# MCU1.net
KiCad netlist of a schematic drawn in Altium Designer
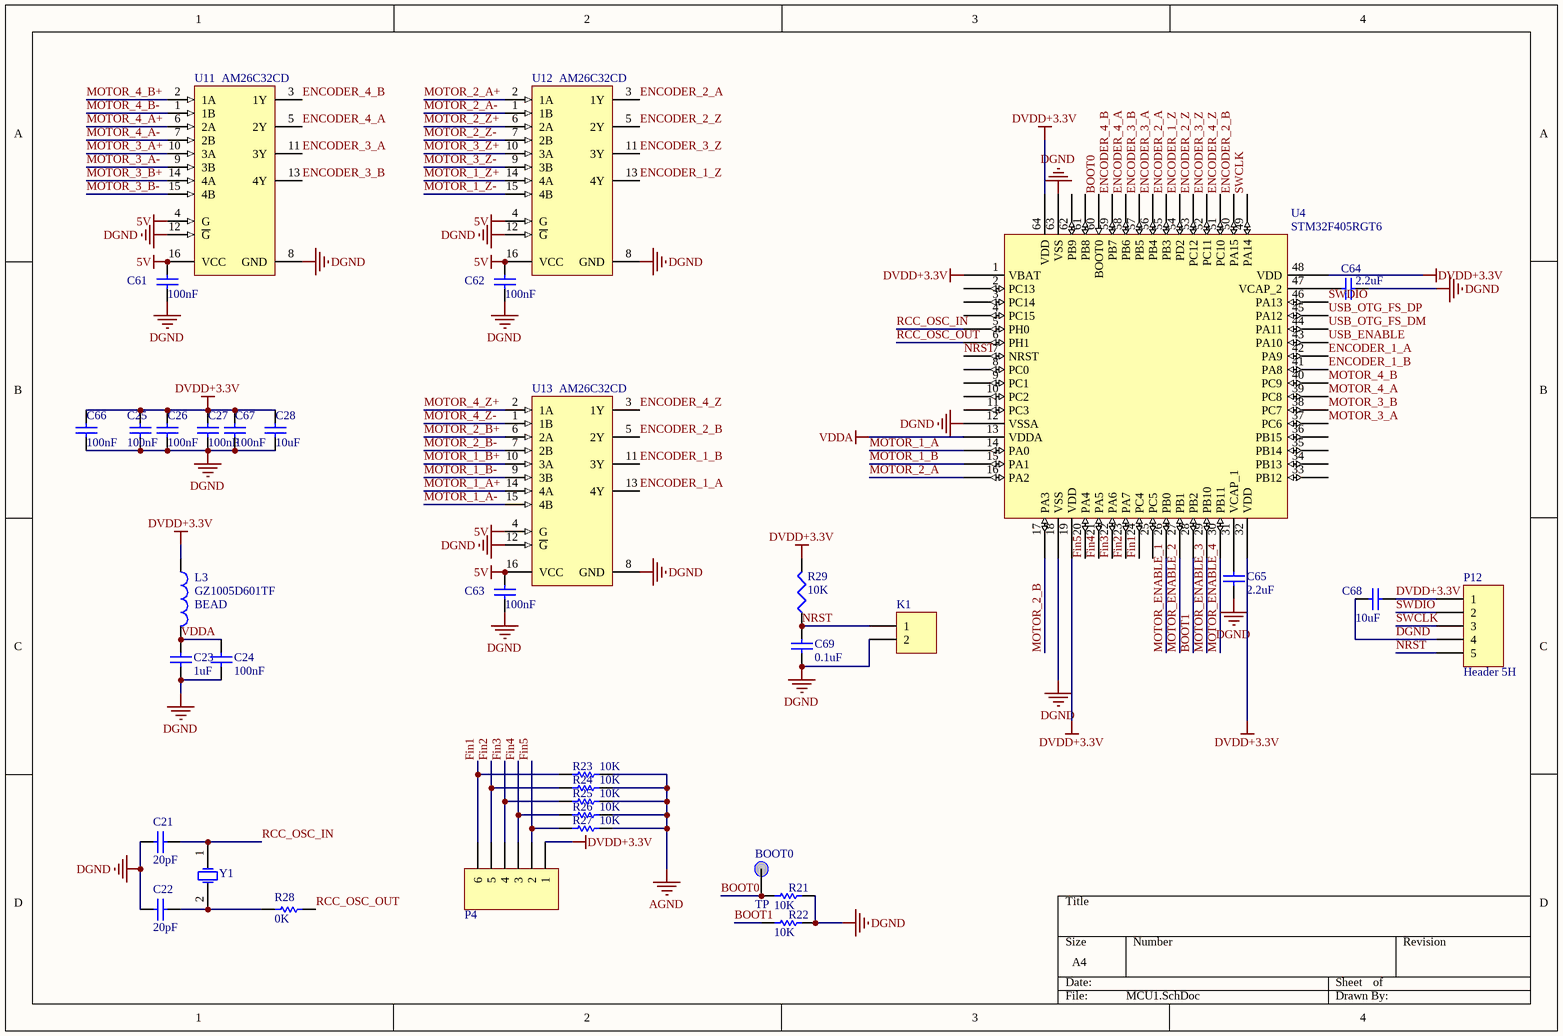
[diagram p0: MCU1.SchDoc]

(export (version "E")
  (design (tool "Eeschema 10.0.6"))
  (components
    (comp (ref "BOOT0") (value "TP") (footprint "TestPort") (libsource (lib "CTs_FYF") (part "TestPoint")))
    (comp (ref "C21")
      (value "20pF")
      (footprint "0402")
      (description "Capacitor")
      (fields (field (name "PUBLISHER") "Altium Limited"))
      (libsource (lib "Miscellaneous Devices") (part "Cap"))
    )
    (comp (ref "C22")
      (value "20pF")
      (footprint "0402")
      (description "Capacitor")
      (fields (field (name "PUBLISHER") "Altium Limited"))
      (libsource (lib "Miscellaneous Devices") (part "Cap"))
    )
    (comp (ref "C23")
      (value "1uF")
      (footprint "1608[0603]")
      (description "Capacitor")
      (fields (field (name "PUBLISHER") "Altium Limited"))
      (libsource (lib "Miscellaneous Devices") (part "Cap"))
    )
    (comp (ref "C24")
      (value "100nF")
      (footprint "1608[0603]")
      (description "Capacitor")
      (fields (field (name "PUBLISHER") "Altium Limited"))
      (libsource (lib "Miscellaneous Devices") (part "Cap"))
    )
    (comp (ref "C25")
      (value "100nF")
      (footprint "1608[0603]")
      (description "Capacitor")
      (fields (field (name "PUBLISHER") "Altium Limited"))
      (libsource (lib "Miscellaneous Devices") (part "Cap"))
    )
    (comp (ref "C26")
      (value "100nF")
      (footprint "1608[0603]")
      (description "Capacitor")
      (fields (field (name "PUBLISHER") "Altium Limited"))
      (libsource (lib "Miscellaneous Devices") (part "Cap"))
    )
    (comp (ref "C27")
      (value "100nF")
      (footprint "1608[0603]")
      (description "Capacitor")
      (fields (field (name "PUBLISHER") "Altium Limited"))
      (libsource (lib "Miscellaneous Devices") (part "Cap"))
    )
    (comp (ref "C28")
      (value "10uF")
      (footprint "1608[0603]")
      (description "Capacitor")
      (fields (field (name "PUBLISHER") "Altium Limited"))
      (libsource (lib "Miscellaneous Devices") (part "Cap"))
    )
    (comp (ref "C61")
      (value "100nF")
      (footprint "1608[0603]")
      (description "Capacitor")
      (fields (field (name "PUBLISHER") "Altium Limited"))
      (libsource (lib "Miscellaneous Devices") (part "Cap"))
    )
    (comp (ref "C62")
      (value "100nF")
      (footprint "1608[0603]")
      (description "Capacitor")
      (fields (field (name "PUBLISHER") "Altium Limited"))
      (libsource (lib "Miscellaneous Devices") (part "Cap"))
    )
    (comp (ref "C63")
      (value "100nF")
      (footprint "1608[0603]")
      (description "Capacitor")
      (fields (field (name "PUBLISHER") "Altium Limited"))
      (libsource (lib "Miscellaneous Devices") (part "Cap"))
    )
    (comp (ref "C64")
      (value "2.2uF")
      (footprint "1608[0603]")
      (description "Capacitor")
      (fields (field (name "PUBLISHER") "Altium Limited"))
      (libsource (lib "Miscellaneous Devices") (part "Cap"))
    )
    (comp (ref "C65")
      (value "2.2uF")
      (footprint "1608[0603]")
      (description "Capacitor")
      (fields (field (name "PUBLISHER") "Altium Limited"))
      (libsource (lib "Miscellaneous Devices") (part "Cap"))
    )
    (comp (ref "C66")
      (value "100nF")
      (footprint "1608[0603]")
      (description "Capacitor")
      (fields (field (name "PUBLISHER") "Altium Limited"))
      (libsource (lib "Miscellaneous Devices") (part "Cap"))
    )
    (comp (ref "C67")
      (value "100nF")
      (footprint "1608[0603]")
      (description "Capacitor")
      (fields (field (name "PUBLISHER") "Altium Limited"))
      (libsource (lib "Miscellaneous Devices") (part "Cap"))
    )
    (comp (ref "C68")
      (value "10uF")
      (footprint "1608[0603]")
      (description "Capacitor")
      (fields (field (name "PUBLISHER") "Altium Limited"))
      (libsource (lib "Miscellaneous Devices") (part "Cap"))
    )
    (comp (ref "C69")
      (value "0.1uF")
      (footprint "1608[0603]")
      (description "Capacitor")
      (fields (field (name "PUBLISHER") "Altium Limited"))
      (libsource (lib "Miscellaneous Devices") (part "Cap"))
    )
    (comp (ref "K1")
      (value "Header 2")
      (footprint "Button")
      (description "Header, 2-Pin")
      (fields (field (name "PUBLISHER") "Altium Limited"))
      (libsource (lib "Miscellaneous Connectors") (part "Header 2"))
    )
    (comp (ref "L3")
      (value "GZ1005D601TF")
      (footprint "0402-A")
      (description "Inductor")
      (fields (field (name "PUBLISHER") "Altium Limited"))
      (libsource (lib "Miscellaneous Devices") (part "Inductor"))
    )
    (comp (ref "P4")
      (value "Header 6")
      (footprint "HDR1X6")
      (description "Header, 6-Pin")
      (fields (field (name "PUBLISHER") "Altium Limited"))
      (libsource (lib "Miscellaneous Connectors") (part "Header 6"))
    )
    (comp (ref "P12")
      (value "Header 5H")
      (footprint "HDR1X5H")
      (description "Header, 5-Pin, Right Angle")
      (fields (field (name "PUBLISHER") "Altium Limited"))
      (libsource (lib "Miscellaneous Connectors") (part "Header 5H"))
    )
    (comp (ref "R21")
      (value "10K")
      (footprint "J1-0603")
      (description "Resistor")
      (fields (field (name "PUBLISHER") "Altium Limited"))
      (libsource (lib "Miscellaneous Devices") (part "Res1"))
    )
    (comp (ref "R22")
      (value "10K")
      (footprint "J1-0603")
      (description "Resistor")
      (fields (field (name "PUBLISHER") "Altium Limited"))
      (libsource (lib "Miscellaneous Devices") (part "Res1"))
    )
    (comp (ref "R23")
      (value "10K")
      (footprint "RES[0402]")
      (description "Resistor")
      (fields (field (name "PUBLISHER") "Altium Limited"))
      (libsource (lib "Miscellaneous Devices") (part "Res1"))
    )
    (comp (ref "R24")
      (value "10K")
      (footprint "RES[0402]")
      (description "Resistor")
      (fields (field (name "PUBLISHER") "Altium Limited"))
      (libsource (lib "Miscellaneous Devices") (part "Res1"))
    )
    (comp (ref "R25")
      (value "10K")
      (footprint "RES[0402]")
      (description "Resistor")
      (fields (field (name "PUBLISHER") "Altium Limited"))
      (libsource (lib "Miscellaneous Devices") (part "Res1"))
    )
    (comp (ref "R26")
      (value "10K")
      (footprint "RES[0402]")
      (description "Resistor")
      (fields (field (name "PUBLISHER") "Altium Limited"))
      (libsource (lib "Miscellaneous Devices") (part "Res1"))
    )
    (comp (ref "R27")
      (value "10K")
      (footprint "RES[0402]")
      (description "Resistor")
      (fields (field (name "PUBLISHER") "Altium Limited"))
      (libsource (lib "Miscellaneous Devices") (part "Res1"))
    )
    (comp (ref "R28")
      (value "0K")
      (footprint "J1-0603")
      (description "Resistor")
      (fields (field (name "PUBLISHER") "Altium Limited"))
      (libsource (lib "Miscellaneous Devices") (part "Res1"))
    )
    (comp (ref "R29")
      (value "10K")
      (footprint "J1-0603")
      (description "Resistor")
      (fields (field (name "PUBLISHER") "Altium Limited"))
      (libsource (lib "Miscellaneous Devices") (part "Res3"))
    )
    (comp (ref "U4")
      (value "STM32F405RGT6")
      (footprint "STM32F405RGT6")
      (description "IC MCU 32BIT 1MB FLASH 64LQFP")
      (libsource (lib "STM32F405RGT6") (part "STM32F405RGT6"))
    )
    (comp (ref "U11")
      (value "AM26C32CD")
      (footprint "D16_L")
      (fields (field (name "MANUFACTURER") "Texas Instruments"))
      (libsource (lib "Texas Instruments Interface RS-422") (part "AM26C32CD"))
    )
    (comp (ref "U12")
      (value "AM26C32CD")
      (footprint "D16_L")
      (fields (field (name "MANUFACTURER") "Texas Instruments"))
      (libsource (lib "Texas Instruments Interface RS-422") (part "AM26C32CD"))
    )
    (comp (ref "U13")
      (value "AM26C32CD")
      (footprint "D16_L")
      (fields (field (name "MANUFACTURER") "Texas Instruments"))
      (libsource (lib "Texas Instruments Interface RS-422") (part "AM26C32CD"))
    )
    (comp (ref "Y1")
      (value "XTAL")
      (footprint "Crystal_HCM49")
      (description "Crystal Oscillator")
      (fields (field (name "PUBLISHER") "Altium Limited"))
      (libsource (lib "Miscellaneous Devices") (part "XTAL"))
    )
  )
  (nets
    (net (code "1") (name "/BOOT0") (class "Default")
      (node (ref "BOOT0") (pin "0") (pinfunction "0_0") (pintype "passive"))
      (node (ref "R21") (pin "1") (pinfunction "1_1") (pintype "passive"))
      (node (ref "U4") (pin "60") (pinfunction "BOOT0_60") (pintype "input"))
    )
    (net (code "2") (name "/BOOT1") (class "Default")
      (node (ref "R22") (pin "1") (pinfunction "1_1") (pintype "passive"))
      (node (ref "U4") (pin "28") (pinfunction "PB2_28") (pintype "bidirectional"))
    )
    (net (code "3") (name "/ENCODER_1_A") (class "Default")
      (node (ref "U13") (pin "13") (pinfunction "4Y_13") (pintype "tri_state"))
      (node (ref "U4") (pin "42") (pinfunction "PA9_42") (pintype "bidirectional"))
    )
    (net (code "4") (name "/ENCODER_1_B") (class "Default")
      (node (ref "U13") (pin "11") (pinfunction "3Y_11") (pintype "tri_state"))
      (node (ref "U4") (pin "41") (pinfunction "PA8_41") (pintype "bidirectional"))
    )
    (net (code "5") (name "/ENCODER_1_Z") (class "Default")
      (node (ref "U12") (pin "13") (pinfunction "4Y_13") (pintype "tri_state"))
      (node (ref "U4") (pin "54") (pinfunction "PD2_54") (pintype "bidirectional"))
    )
    (net (code "6") (name "/ENCODER_2_A") (class "Default")
      (node (ref "U12") (pin "3") (pinfunction "1Y_3") (pintype "tri_state"))
      (node (ref "U4") (pin "55") (pinfunction "PB3_55") (pintype "bidirectional"))
    )
    (net (code "7") (name "/ENCODER_2_B") (class "Default")
      (node (ref "U13") (pin "5") (pinfunction "2Y_5") (pintype "tri_state"))
      (node (ref "U4") (pin "50") (pinfunction "PA15_50") (pintype "bidirectional"))
    )
    (net (code "8") (name "/ENCODER_2_Z") (class "Default")
      (node (ref "U12") (pin "5") (pinfunction "2Y_5") (pintype "tri_state"))
      (node (ref "U4") (pin "53") (pinfunction "PC12_53") (pintype "bidirectional"))
    )
    (net (code "9") (name "/ENCODER_3_A") (class "Default")
      (node (ref "U11") (pin "11") (pinfunction "3Y_11") (pintype "tri_state"))
      (node (ref "U4") (pin "56") (pinfunction "PB4_56") (pintype "bidirectional"))
    )
    (net (code "10") (name "/ENCODER_3_B") (class "Default")
      (node (ref "U11") (pin "13") (pinfunction "4Y_13") (pintype "tri_state"))
      (node (ref "U4") (pin "57") (pinfunction "PB5_57") (pintype "bidirectional"))
    )
    (net (code "11") (name "/ENCODER_3_Z") (class "Default")
      (node (ref "U12") (pin "11") (pinfunction "3Y_11") (pintype "tri_state"))
      (node (ref "U4") (pin "52") (pinfunction "PC11_52") (pintype "bidirectional"))
    )
    (net (code "12") (name "/ENCODER_4_A") (class "Default")
      (node (ref "U11") (pin "5") (pinfunction "2Y_5") (pintype "tri_state"))
      (node (ref "U4") (pin "58") (pinfunction "PB6_58") (pintype "bidirectional"))
    )
    (net (code "13") (name "/ENCODER_4_B") (class "Default")
      (node (ref "U11") (pin "3") (pinfunction "1Y_3") (pintype "tri_state"))
      (node (ref "U4") (pin "59") (pinfunction "PB7_59") (pintype "bidirectional"))
    )
    (net (code "14") (name "/ENCODER_4_Z") (class "Default")
      (node (ref "U13") (pin "3") (pinfunction "1Y_3") (pintype "tri_state"))
      (node (ref "U4") (pin "51") (pinfunction "PC10_51") (pintype "bidirectional"))
    )
    (net (code "15") (name "/Fin1") (class "Default")
      (node (ref "P4") (pin "6") (pinfunction "6_6") (pintype "passive"))
      (node (ref "R23") (pin "1") (pinfunction "1_1") (pintype "passive"))
      (node (ref "U4") (pin "24") (pinfunction "PC4_24") (pintype "bidirectional"))
    )
    (net (code "16") (name "/Fin2") (class "Default")
      (node (ref "P4") (pin "5") (pinfunction "5_5") (pintype "passive"))
      (node (ref "R24") (pin "1") (pinfunction "1_1") (pintype "passive"))
      (node (ref "U4") (pin "23") (pinfunction "PA7_23") (pintype "bidirectional"))
    )
    (net (code "17") (name "/Fin3") (class "Default")
      (node (ref "P4") (pin "4") (pinfunction "4_4") (pintype "passive"))
      (node (ref "R25") (pin "1") (pinfunction "1_1") (pintype "passive"))
      (node (ref "U4") (pin "22") (pinfunction "PA6_22") (pintype "bidirectional"))
    )
    (net (code "18") (name "/Fin4") (class "Default")
      (node (ref "P4") (pin "3") (pinfunction "3_3") (pintype "passive"))
      (node (ref "R26") (pin "1") (pinfunction "1_1") (pintype "passive"))
      (node (ref "U4") (pin "21") (pinfunction "PA5_21") (pintype "bidirectional"))
    )
    (net (code "19") (name "/Fin5") (class "Default")
      (node (ref "P4") (pin "2") (pinfunction "2_2") (pintype "passive"))
      (node (ref "R27") (pin "1") (pinfunction "1_1") (pintype "passive"))
      (node (ref "U4") (pin "20") (pinfunction "PA4_20") (pintype "bidirectional"))
    )
    (net (code "20") (name "/MOTOR_1_A") (class "Default")
      (node (ref "U4") (pin "14") (pinfunction "PA0_14") (pintype "bidirectional"))
    )
    (net (code "21") (name "/MOTOR_1_A+") (class "Default")
      (node (ref "U13") (pin "14") (pinfunction "4A_14") (pintype "input"))
    )
    (net (code "22") (name "/MOTOR_1_A-") (class "Default")
      (node (ref "U13") (pin "15") (pinfunction "4B_15") (pintype "input"))
    )
    (net (code "23") (name "/MOTOR_1_B") (class "Default")
      (node (ref "U4") (pin "15") (pinfunction "PA1_15") (pintype "bidirectional"))
    )
    (net (code "24") (name "/MOTOR_1_B+") (class "Default")
      (node (ref "U13") (pin "10") (pinfunction "3A_10") (pintype "input"))
    )
    (net (code "25") (name "/MOTOR_1_B-") (class "Default")
      (node (ref "U13") (pin "9") (pinfunction "3B_9") (pintype "input"))
    )
    (net (code "26") (name "/MOTOR_1_Z+") (class "Default")
      (node (ref "U12") (pin "14") (pinfunction "4A_14") (pintype "input"))
    )
    (net (code "27") (name "/MOTOR_1_Z-") (class "Default")
      (node (ref "U12") (pin "15") (pinfunction "4B_15") (pintype "input"))
    )
    (net (code "28") (name "/MOTOR_2_A") (class "Default")
      (node (ref "U4") (pin "16") (pinfunction "PA2_16") (pintype "bidirectional"))
    )
    (net (code "29") (name "/MOTOR_2_A+") (class "Default")
      (node (ref "U12") (pin "2") (pinfunction "1A_2") (pintype "input"))
    )
    (net (code "30") (name "/MOTOR_2_A-") (class "Default")
      (node (ref "U12") (pin "1") (pinfunction "1B_1") (pintype "input"))
    )
    (net (code "31") (name "/MOTOR_2_B") (class "Default")
      (node (ref "U4") (pin "17") (pinfunction "PA3_17") (pintype "bidirectional"))
    )
    (net (code "32") (name "/MOTOR_2_B+") (class "Default")
      (node (ref "U13") (pin "6") (pinfunction "2A_6") (pintype "input"))
    )
    (net (code "33") (name "/MOTOR_2_B-") (class "Default")
      (node (ref "U13") (pin "7") (pinfunction "2B_7") (pintype "input"))
    )
    (net (code "34") (name "/MOTOR_2_Z+") (class "Default")
      (node (ref "U12") (pin "6") (pinfunction "2A_6") (pintype "input"))
    )
    (net (code "35") (name "/MOTOR_2_Z-") (class "Default")
      (node (ref "U12") (pin "7") (pinfunction "2B_7") (pintype "input"))
    )
    (net (code "36") (name "/MOTOR_3_A") (class "Default")
      (node (ref "U4") (pin "37") (pinfunction "PC6_37") (pintype "bidirectional"))
    )
    (net (code "37") (name "/MOTOR_3_A+") (class "Default")
      (node (ref "U11") (pin "10") (pinfunction "3A_10") (pintype "input"))
    )
    (net (code "38") (name "/MOTOR_3_A-") (class "Default")
      (node (ref "U11") (pin "9") (pinfunction "3B_9") (pintype "input"))
    )
    (net (code "39") (name "/MOTOR_3_B") (class "Default")
      (node (ref "U4") (pin "38") (pinfunction "PC7_38") (pintype "bidirectional"))
    )
    (net (code "40") (name "/MOTOR_3_B+") (class "Default")
      (node (ref "U11") (pin "14") (pinfunction "4A_14") (pintype "input"))
    )
    (net (code "41") (name "/MOTOR_3_B-") (class "Default")
      (node (ref "U11") (pin "15") (pinfunction "4B_15") (pintype "input"))
    )
    (net (code "42") (name "/MOTOR_3_Z+") (class "Default")
      (node (ref "U12") (pin "10") (pinfunction "3A_10") (pintype "input"))
    )
    (net (code "43") (name "/MOTOR_3_Z-") (class "Default")
      (node (ref "U12") (pin "9") (pinfunction "3B_9") (pintype "input"))
    )
    (net (code "44") (name "/MOTOR_4_A") (class "Default")
      (node (ref "U4") (pin "39") (pinfunction "PC8_39") (pintype "bidirectional"))
    )
    (net (code "45") (name "/MOTOR_4_A+") (class "Default")
      (node (ref "U11") (pin "6") (pinfunction "2A_6") (pintype "input"))
    )
    (net (code "46") (name "/MOTOR_4_A-") (class "Default")
      (node (ref "U11") (pin "7") (pinfunction "2B_7") (pintype "input"))
    )
    (net (code "47") (name "/MOTOR_4_B") (class "Default")
      (node (ref "U4") (pin "40") (pinfunction "PC9_40") (pintype "bidirectional"))
    )
    (net (code "48") (name "/MOTOR_4_B+") (class "Default")
      (node (ref "U11") (pin "2") (pinfunction "1A_2") (pintype "input"))
    )
    (net (code "49") (name "/MOTOR_4_B-") (class "Default")
      (node (ref "U11") (pin "1") (pinfunction "1B_1") (pintype "input"))
    )
    (net (code "50") (name "/MOTOR_4_Z+") (class "Default")
      (node (ref "U13") (pin "2") (pinfunction "1A_2") (pintype "input"))
    )
    (net (code "51") (name "/MOTOR_4_Z-") (class "Default")
      (node (ref "U13") (pin "1") (pinfunction "1B_1") (pintype "input"))
    )
    (net (code "52") (name "/MOTOR_ENABLE_1") (class "Default")
      (node (ref "U4") (pin "26") (pinfunction "PB0_26") (pintype "bidirectional"))
    )
    (net (code "53") (name "/MOTOR_ENABLE_2") (class "Default")
      (node (ref "U4") (pin "27") (pinfunction "PB1_27") (pintype "bidirectional"))
    )
    (net (code "54") (name "/MOTOR_ENABLE_3") (class "Default")
      (node (ref "U4") (pin "29") (pinfunction "PB10_29") (pintype "bidirectional"))
    )
    (net (code "55") (name "/MOTOR_ENABLE_4") (class "Default")
      (node (ref "U4") (pin "30") (pinfunction "PB11_30") (pintype "bidirectional"))
    )
    (net (code "56") (name "/NRST") (class "Default")
      (node (ref "C69") (pin "2") (pinfunction "2_2") (pintype "passive"))
      (node (ref "K1") (pin "1") (pinfunction "1_1") (pintype "passive"))
      (node (ref "P12") (pin "5") (pinfunction "5_5") (pintype "passive"))
      (node (ref "R29") (pin "1") (pinfunction "1_1") (pintype "passive"))
      (node (ref "U4") (pin "7") (pinfunction "NRST_7") (pintype "bidirectional"))
    )
    (net (code "57") (name "/RCC_OSC_IN") (class "Default")
      (node (ref "C21") (pin "2") (pinfunction "2_2") (pintype "passive"))
      (node (ref "U4") (pin "5") (pinfunction "PH0_5") (pintype "bidirectional"))
      (node (ref "Y1") (pin "1") (pinfunction "OSC1_1") (pintype "passive"))
    )
    (net (code "58") (name "/RCC_OSC_OUT") (class "Default")
      (node (ref "R28") (pin "2") (pinfunction "2_2") (pintype "passive"))
      (node (ref "U4") (pin "6") (pinfunction "PH1_6") (pintype "bidirectional"))
    )
    (net (code "59") (name "/SWCLK") (class "Default")
      (node (ref "P12") (pin "3") (pinfunction "3_3") (pintype "passive"))
      (node (ref "U4") (pin "49") (pinfunction "PA14_49") (pintype "bidirectional"))
    )
    (net (code "60") (name "/SWDIO") (class "Default")
      (node (ref "P12") (pin "2") (pinfunction "2_2") (pintype "passive"))
      (node (ref "U4") (pin "46") (pinfunction "PA13_46") (pintype "bidirectional"))
    )
    (net (code "61") (name "/USB_ENABLE") (class "Default")
      (node (ref "U4") (pin "43") (pinfunction "PA10_43") (pintype "bidirectional"))
    )
    (net (code "62") (name "/USB_OTG_FS_DM") (class "Default")
      (node (ref "U4") (pin "44") (pinfunction "PA11_44") (pintype "bidirectional"))
    )
    (net (code "63") (name "/USB_OTG_FS_DP") (class "Default")
      (node (ref "U4") (pin "45") (pinfunction "PA12_45") (pintype "bidirectional"))
    )
    (net (code "64") (name "5V") (class "Default")
      (node (ref "C61") (pin "2") (pinfunction "2_2") (pintype "passive"))
      (node (ref "C62") (pin "2") (pinfunction "2_2") (pintype "passive"))
      (node (ref "C63") (pin "2") (pinfunction "2_2") (pintype "passive"))
      (node (ref "U11") (pin "16") (pinfunction "VCC_16") (pintype "power_in"))
      (node (ref "U11") (pin "4") (pinfunction "G_4") (pintype "input"))
      (node (ref "U12") (pin "16") (pinfunction "VCC_16") (pintype "power_in"))
      (node (ref "U12") (pin "4") (pinfunction "G_4") (pintype "input"))
      (node (ref "U13") (pin "16") (pinfunction "VCC_16") (pintype "power_in"))
      (node (ref "U13") (pin "4") (pinfunction "G_4") (pintype "input"))
    )
    (net (code "65") (name "AGND") (class "Default")
      (node (ref "R23") (pin "2") (pinfunction "2_2") (pintype "passive"))
      (node (ref "R24") (pin "2") (pinfunction "2_2") (pintype "passive"))
      (node (ref "R25") (pin "2") (pinfunction "2_2") (pintype "passive"))
      (node (ref "R26") (pin "2") (pinfunction "2_2") (pintype "passive"))
      (node (ref "R27") (pin "2") (pinfunction "2_2") (pintype "passive"))
    )
    (net (code "66") (name "DGND") (class "Default")
      (node (ref "C21") (pin "1") (pinfunction "1_1") (pintype "passive"))
      (node (ref "C22") (pin "1") (pinfunction "1_1") (pintype "passive"))
      (node (ref "C23") (pin "1") (pinfunction "1_1") (pintype "passive"))
      (node (ref "C24") (pin "1") (pinfunction "1_1") (pintype "passive"))
      (node (ref "C25") (pin "1") (pinfunction "1_1") (pintype "passive"))
      (node (ref "C26") (pin "1") (pinfunction "1_1") (pintype "passive"))
      (node (ref "C27") (pin "1") (pinfunction "1_1") (pintype "passive"))
      (node (ref "C28") (pin "1") (pinfunction "1_1") (pintype "passive"))
      (node (ref "C61") (pin "1") (pinfunction "1_1") (pintype "passive"))
      (node (ref "C62") (pin "1") (pinfunction "1_1") (pintype "passive"))
      (node (ref "C63") (pin "1") (pinfunction "1_1") (pintype "passive"))
      (node (ref "C64") (pin "2") (pinfunction "2_2") (pintype "passive"))
      (node (ref "C65") (pin "1") (pinfunction "1_1") (pintype "passive"))
      (node (ref "C66") (pin "1") (pinfunction "1_1") (pintype "passive"))
      (node (ref "C67") (pin "1") (pinfunction "1_1") (pintype "passive"))
      (node (ref "C68") (pin "1") (pinfunction "1_1") (pintype "passive"))
      (node (ref "C69") (pin "1") (pinfunction "1_1") (pintype "passive"))
      (node (ref "K1") (pin "2") (pinfunction "2_2") (pintype "passive"))
      (node (ref "P12") (pin "4") (pinfunction "4_4") (pintype "passive"))
      (node (ref "R21") (pin "2") (pinfunction "2_2") (pintype "passive"))
      (node (ref "R22") (pin "2") (pinfunction "2_2") (pintype "passive"))
      (node (ref "U11") (pin "12") (pinfunction "~{G}_12") (pintype "input"))
      (node (ref "U11") (pin "8") (pinfunction "GND_8") (pintype "power_in"))
      (node (ref "U12") (pin "12") (pinfunction "~{G}_12") (pintype "input"))
      (node (ref "U12") (pin "8") (pinfunction "GND_8") (pintype "power_in"))
      (node (ref "U13") (pin "12") (pinfunction "~{G}_12") (pintype "input"))
      (node (ref "U13") (pin "8") (pinfunction "GND_8") (pintype "power_in"))
      (node (ref "U4") (pin "12") (pinfunction "VSSA_12") (pintype "power_in"))
      (node (ref "U4") (pin "18") (pinfunction "VSS_18") (pintype "power_in"))
      (node (ref "U4") (pin "63") (pinfunction "VSS_63") (pintype "power_in"))
    )
    (net (code "67") (name "DVDD+3.3V") (class "Default")
      (node (ref "C25") (pin "2") (pinfunction "2_2") (pintype "passive"))
      (node (ref "C26") (pin "2") (pinfunction "2_2") (pintype "passive"))
      (node (ref "C27") (pin "2") (pinfunction "2_2") (pintype "passive"))
      (node (ref "C28") (pin "2") (pinfunction "2_2") (pintype "passive"))
      (node (ref "C66") (pin "2") (pinfunction "2_2") (pintype "passive"))
      (node (ref "C67") (pin "2") (pinfunction "2_2") (pintype "passive"))
      (node (ref "C68") (pin "2") (pinfunction "2_2") (pintype "passive"))
      (node (ref "L3") (pin "1") (pinfunction "1_1") (pintype "passive"))
      (node (ref "P12") (pin "1") (pinfunction "1_1") (pintype "passive"))
      (node (ref "P4") (pin "1") (pinfunction "1_1") (pintype "passive"))
      (node (ref "R29") (pin "2") (pinfunction "2_2") (pintype "passive"))
      (node (ref "U4") (pin "1") (pinfunction "VBAT_1") (pintype "passive"))
      (node (ref "U4") (pin "19") (pinfunction "VDD_19") (pintype "power_in"))
      (node (ref "U4") (pin "32") (pinfunction "VDD_32") (pintype "power_in"))
      (node (ref "U4") (pin "48") (pinfunction "VDD_48") (pintype "power_in"))
      (node (ref "U4") (pin "64") (pinfunction "VDD_64") (pintype "power_in"))
    )
    (net (code "68") (name "Net-(U4-VCAP_1)") (class "Default")
      (node (ref "C65") (pin "2") (pinfunction "2_2") (pintype "passive"))
      (node (ref "U4") (pin "31") (pinfunction "VCAP_1_31") (pintype "power_in"))
    )
    (net (code "69") (name "Net-(U4-VCAP_2)") (class "Default")
      (node (ref "C64") (pin "1") (pinfunction "1_1") (pintype "passive"))
      (node (ref "U4") (pin "47") (pinfunction "VCAP_2_47") (pintype "power_in"))
    )
    (net (code "70") (name "Net-(Y1-OSC2)") (class "Default")
      (node (ref "C22") (pin "2") (pinfunction "2_2") (pintype "passive"))
      (node (ref "R28") (pin "1") (pinfunction "1_1") (pintype "passive"))
      (node (ref "Y1") (pin "2") (pinfunction "OSC2_2") (pintype "passive"))
    )
    (net (code "71") (name "VDDA") (class "Default")
      (node (ref "C23") (pin "2") (pinfunction "2_2") (pintype "passive"))
      (node (ref "C24") (pin "2") (pinfunction "2_2") (pintype "passive"))
      (node (ref "L3") (pin "2") (pinfunction "2_2") (pintype "passive"))
      (node (ref "U4") (pin "13") (pinfunction "VDDA_13") (pintype "power_in"))
    )
    (net (code "72") (name "unconnected-(U4-PB8-Pad61)") (class "Default")
      (node (ref "U4") (pin "61") (pinfunction "PB8_61") (pintype "bidirectional"))
    )
    (net (code "73") (name "unconnected-(U4-PB9-Pad62)") (class "Default")
      (node (ref "U4") (pin "62") (pinfunction "PB9_62") (pintype "bidirectional"))
    )
    (net (code "74") (name "unconnected-(U4-PB12-Pad33)") (class "Default")
      (node (ref "U4") (pin "33") (pinfunction "PB12_33") (pintype "bidirectional"))
    )
    (net (code "75") (name "unconnected-(U4-PB13-Pad34)") (class "Default")
      (node (ref "U4") (pin "34") (pinfunction "PB13_34") (pintype "bidirectional"))
    )
    (net (code "76") (name "unconnected-(U4-PB14-Pad35)") (class "Default")
      (node (ref "U4") (pin "35") (pinfunction "PB14_35") (pintype "bidirectional"))
    )
    (net (code "77") (name "unconnected-(U4-PB15-Pad36)") (class "Default")
      (node (ref "U4") (pin "36") (pinfunction "PB15_36") (pintype "bidirectional"))
    )
    (net (code "78") (name "unconnected-(U4-PC0-Pad8)") (class "Default")
      (node (ref "U4") (pin "8") (pinfunction "PC0_8") (pintype "bidirectional"))
    )
    (net (code "79") (name "unconnected-(U4-PC1-Pad9)") (class "Default")
      (node (ref "U4") (pin "9") (pinfunction "PC1_9") (pintype "bidirectional"))
    )
    (net (code "80") (name "unconnected-(U4-PC2-Pad10)") (class "Default")
      (node (ref "U4") (pin "10") (pinfunction "PC2_10") (pintype "bidirectional"))
    )
    (net (code "81") (name "unconnected-(U4-PC3-Pad11)") (class "Default")
      (node (ref "U4") (pin "11") (pinfunction "PC3_11") (pintype "bidirectional"))
    )
    (net (code "82") (name "unconnected-(U4-PC5-Pad25)") (class "Default")
      (node (ref "U4") (pin "25") (pinfunction "PC5_25") (pintype "bidirectional"))
    )
    (net (code "83") (name "unconnected-(U4-PC13-Pad2)") (class "Default")
      (node (ref "U4") (pin "2") (pinfunction "PC13_2") (pintype "bidirectional"))
    )
    (net (code "84") (name "unconnected-(U4-PC14-Pad3)") (class "Default")
      (node (ref "U4") (pin "3") (pinfunction "PC14_3") (pintype "bidirectional"))
    )
    (net (code "85") (name "unconnected-(U4-PC15-Pad4)") (class "Default")
      (node (ref "U4") (pin "4") (pinfunction "PC15_4") (pintype "bidirectional"))
    )
  )
)
